# panel_jack_board.net
KiCad netlist of a schematic drawn in EAGLE
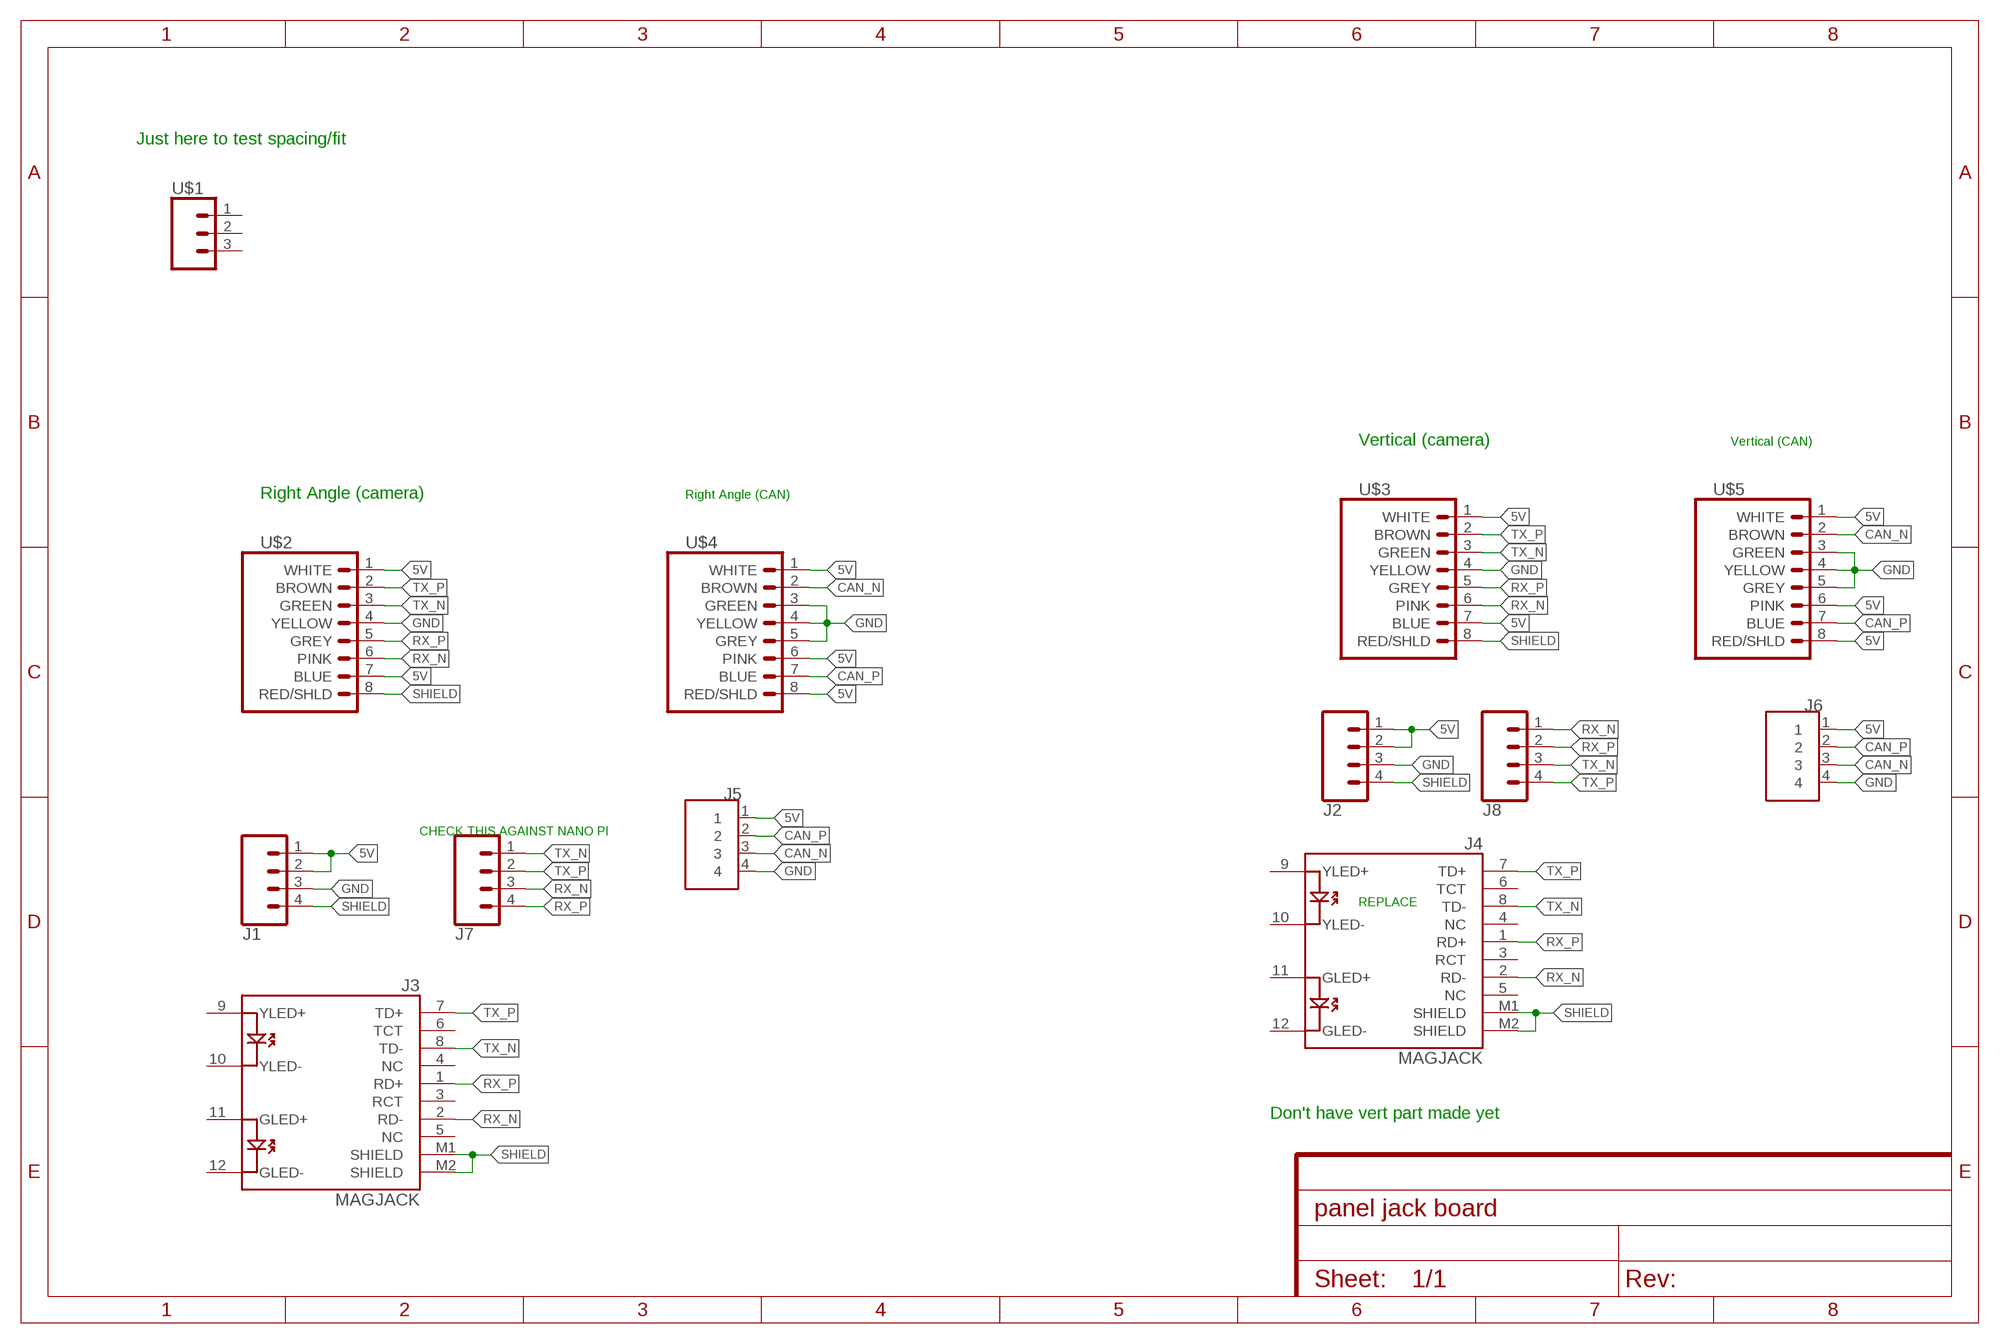
[diagram p0: schematic, sheet 1]

(export (version "E")
  (design (tool "Eeschema 10.0.6"))
  (components
    (comp (ref "J1")
      (value "PXC-PTSM-04-V-1778573")
      (footprint "eagle-import:PXC-PTSM-04-V-1778573")
      (libsource (lib "eagle-import") (part "PXC-PTSM-04-V-1778573"))
    )
    (comp (ref "J2")
      (value "PXC-PTSM-04-V-1778573")
      (footprint "eagle-import:PXC-PTSM-04-V-1778573")
      (libsource (lib "eagle-import") (part "PXC-PTSM-04-V-1778573"))
    )
    (comp (ref "J3")
      (value "MAGJACK")
      (footprint "eagle-import:MAGJACK")
      (libsource (lib "eagle-import") (part "MAGJACK"))
    )
    (comp (ref "J4")
      (value "MAGJACK")
      (footprint "eagle-import:MAGJACK")
      (libsource (lib "eagle-import") (part "MAGJACK"))
    )
    (comp (ref "J5")
      (value "284512-4")
      (footprint "eagle-import:TE_284512-4")
      (fields (field (name "MANUFACTURER") "TE"))
      (libsource (lib "eagle-import") (part "284512-4"))
    )
    (comp (ref "J6")
      (value "284512-4")
      (footprint "eagle-import:TE_284512-4")
      (fields (field (name "MANUFACTURER") "TE"))
      (libsource (lib "eagle-import") (part "284512-4"))
    )
    (comp (ref "J7")
      (value "PXC-PTSM-04-RA-1778641")
      (footprint "eagle-import:PXC-PTSM-04-RA-1778641")
      (libsource (lib "eagle-import") (part "PXC-PTSM-04-RA-1778641"))
    )
    (comp (ref "J8")
      (value "PXC-PTSM-04-V-1778573")
      (footprint "eagle-import:PXC-PTSM-04-V-1778573")
      (libsource (lib "eagle-import") (part "PXC-PTSM-04-V-1778573"))
    )
    (comp (ref "U$1")
      (value "BULGIN_BUC4000_3")
      (footprint "eagle-import:BULGIN_BUC4000_3")
      (libsource (lib "eagle-import") (part "BULGIN_BUC4000_3"))
    )
    (comp (ref "U$2")
      (value "BINDER_M12_RA_8")
      (footprint "eagle-import:BINDER_M12_RA_8")
      (libsource (lib "eagle-import") (part "BINDER_M12_RA_8"))
    )
    (comp (ref "U$3")
      (value "BINDER_M12_PAR_8_DIP")
      (footprint "eagle-import:BINDER_M12_PAR_8_DIP")
      (libsource (lib "eagle-import") (part "BINDER_M12_PAR_8_DIP"))
    )
    (comp (ref "U$4")
      (value "BINDER_M12_RA_8")
      (footprint "eagle-import:BINDER_M12_RA_8")
      (libsource (lib "eagle-import") (part "BINDER_M12_RA_8"))
    )
    (comp (ref "U$5")
      (value "BINDER_M12_PAR_8_DIP")
      (footprint "eagle-import:BINDER_M12_PAR_8_DIP")
      (libsource (lib "eagle-import") (part "BINDER_M12_PAR_8_DIP"))
    )
  )
  (nets
    (net (code "1") (name "5V") (class "Default")
      (node (ref "J1") (pin "1") (pinfunction "1_1") (pintype "passive"))
      (node (ref "J1") (pin "2") (pinfunction "2_2") (pintype "passive"))
      (node (ref "J2") (pin "1") (pinfunction "1_1") (pintype "passive"))
      (node (ref "J2") (pin "2") (pinfunction "2_2") (pintype "passive"))
      (node (ref "J5") (pin "1") (pinfunction "1_1") (pintype "passive"))
      (node (ref "J6") (pin "1") (pinfunction "1_1") (pintype "passive"))
      (node (ref "U$2") (pin "1") (pinfunction "WHITE_1") (pintype "passive"))
      (node (ref "U$2") (pin "7") (pinfunction "BLUE_7") (pintype "passive"))
      (node (ref "U$3") (pin "1") (pinfunction "WHITE_1") (pintype "passive"))
      (node (ref "U$3") (pin "7") (pinfunction "BLUE_7") (pintype "passive"))
      (node (ref "U$4") (pin "1") (pinfunction "WHITE_1") (pintype "passive"))
      (node (ref "U$4") (pin "6") (pinfunction "PINK_6") (pintype "passive"))
      (node (ref "U$4") (pin "8") (pinfunction "RED/SHLD_8") (pintype "passive"))
      (node (ref "U$5") (pin "1") (pinfunction "WHITE_1") (pintype "passive"))
      (node (ref "U$5") (pin "6") (pinfunction "PINK_6") (pintype "passive"))
      (node (ref "U$5") (pin "8") (pinfunction "RED/SHLD_8") (pintype "passive"))
    )
    (net (code "2") (name "CAN_N") (class "Default")
      (node (ref "J5") (pin "3") (pinfunction "3_3") (pintype "passive"))
      (node (ref "J6") (pin "3") (pinfunction "3_3") (pintype "passive"))
      (node (ref "U$4") (pin "2") (pinfunction "BROWN_2") (pintype "passive"))
      (node (ref "U$5") (pin "2") (pinfunction "BROWN_2") (pintype "passive"))
    )
    (net (code "3") (name "CAN_P") (class "Default")
      (node (ref "J5") (pin "2") (pinfunction "2_2") (pintype "passive"))
      (node (ref "J6") (pin "2") (pinfunction "2_2") (pintype "passive"))
      (node (ref "U$4") (pin "7") (pinfunction "BLUE_7") (pintype "passive"))
      (node (ref "U$5") (pin "7") (pinfunction "BLUE_7") (pintype "passive"))
    )
    (net (code "4") (name "GND") (class "Default")
      (node (ref "J1") (pin "3") (pinfunction "3_3") (pintype "passive"))
      (node (ref "J2") (pin "3") (pinfunction "3_3") (pintype "passive"))
      (node (ref "J5") (pin "4") (pinfunction "4_4") (pintype "passive"))
      (node (ref "J6") (pin "4") (pinfunction "4_4") (pintype "passive"))
      (node (ref "U$2") (pin "4") (pinfunction "YELLOW_4") (pintype "passive"))
      (node (ref "U$3") (pin "4") (pinfunction "YELLOW_4") (pintype "passive"))
      (node (ref "U$4") (pin "3") (pinfunction "GREEN_3") (pintype "passive"))
      (node (ref "U$4") (pin "4") (pinfunction "YELLOW_4") (pintype "passive"))
      (node (ref "U$4") (pin "5") (pinfunction "GREY_5") (pintype "passive"))
      (node (ref "U$5") (pin "3") (pinfunction "GREEN_3") (pintype "passive"))
      (node (ref "U$5") (pin "4") (pinfunction "YELLOW_4") (pintype "passive"))
      (node (ref "U$5") (pin "5") (pinfunction "GREY_5") (pintype "passive"))
    )
    (net (code "5") (name "RX_N") (class "Default")
      (node (ref "J3") (pin "2") (pinfunction "RD-_2") (pintype "bidirectional"))
      (node (ref "J4") (pin "2") (pinfunction "RD-_2") (pintype "bidirectional"))
      (node (ref "J7") (pin "3") (pinfunction "3_3") (pintype "passive"))
      (node (ref "J8") (pin "1") (pinfunction "1_1") (pintype "passive"))
      (node (ref "U$2") (pin "6") (pinfunction "PINK_6") (pintype "passive"))
      (node (ref "U$3") (pin "6") (pinfunction "PINK_6") (pintype "passive"))
    )
    (net (code "6") (name "RX_P") (class "Default")
      (node (ref "J3") (pin "1") (pinfunction "RD+_1") (pintype "bidirectional"))
      (node (ref "J4") (pin "1") (pinfunction "RD+_1") (pintype "bidirectional"))
      (node (ref "J7") (pin "4") (pinfunction "4_4") (pintype "passive"))
      (node (ref "J8") (pin "2") (pinfunction "2_2") (pintype "passive"))
      (node (ref "U$2") (pin "5") (pinfunction "GREY_5") (pintype "passive"))
      (node (ref "U$3") (pin "5") (pinfunction "GREY_5") (pintype "passive"))
    )
    (net (code "7") (name "SHIELD") (class "Default")
      (node (ref "J1") (pin "4") (pinfunction "4_4") (pintype "passive"))
      (node (ref "J2") (pin "4") (pinfunction "4_4") (pintype "passive"))
      (node (ref "J3") (pin "M1") (pinfunction "SHIELD_M1") (pintype "bidirectional"))
      (node (ref "J3") (pin "M2") (pinfunction "SHIELD_M2") (pintype "bidirectional"))
      (node (ref "J4") (pin "M1") (pinfunction "SHIELD_M1") (pintype "bidirectional"))
      (node (ref "J4") (pin "M2") (pinfunction "SHIELD_M2") (pintype "bidirectional"))
      (node (ref "U$2") (pin "8") (pinfunction "RED/SHLD_8") (pintype "passive"))
      (node (ref "U$3") (pin "8") (pinfunction "RED/SHLD_8") (pintype "passive"))
    )
    (net (code "8") (name "TX_N") (class "Default")
      (node (ref "J3") (pin "8") (pinfunction "TD-_8") (pintype "bidirectional"))
      (node (ref "J4") (pin "8") (pinfunction "TD-_8") (pintype "bidirectional"))
      (node (ref "J7") (pin "1") (pinfunction "1_1") (pintype "passive"))
      (node (ref "J8") (pin "3") (pinfunction "3_3") (pintype "passive"))
      (node (ref "U$2") (pin "3") (pinfunction "GREEN_3") (pintype "passive"))
      (node (ref "U$3") (pin "3") (pinfunction "GREEN_3") (pintype "passive"))
    )
    (net (code "9") (name "TX_P") (class "Default")
      (node (ref "J3") (pin "7") (pinfunction "TD+_7") (pintype "bidirectional"))
      (node (ref "J4") (pin "7") (pinfunction "TD+_7") (pintype "bidirectional"))
      (node (ref "J7") (pin "2") (pinfunction "2_2") (pintype "passive"))
      (node (ref "J8") (pin "4") (pinfunction "4_4") (pintype "passive"))
      (node (ref "U$2") (pin "2") (pinfunction "BROWN_2") (pintype "passive"))
      (node (ref "U$3") (pin "2") (pinfunction "BROWN_2") (pintype "passive"))
    )
    (net (code "10") (name "unconnected-(J3-GLED+-Pad11)") (class "Default")
      (node (ref "J3") (pin "11") (pinfunction "GLED+_11") (pintype "bidirectional"))
    )
    (net (code "11") (name "unconnected-(J3-GLED--Pad12)") (class "Default")
      (node (ref "J3") (pin "12") (pinfunction "GLED-_12") (pintype "bidirectional"))
    )
    (net (code "12") (name "unconnected-(J3-NC-Pad4)") (class "Default")
      (node (ref "J3") (pin "4") (pinfunction "NC_4") (pintype "bidirectional"))
    )
    (net (code "13") (name "unconnected-(J3-NC-Pad5)") (class "Default")
      (node (ref "J3") (pin "5") (pinfunction "NC_5") (pintype "bidirectional"))
    )
    (net (code "14") (name "unconnected-(J3-RCT-Pad3)") (class "Default")
      (node (ref "J3") (pin "3") (pinfunction "RCT_3") (pintype "bidirectional"))
    )
    (net (code "15") (name "unconnected-(J3-TCT-Pad6)") (class "Default")
      (node (ref "J3") (pin "6") (pinfunction "TCT_6") (pintype "bidirectional"))
    )
    (net (code "16") (name "unconnected-(J3-YLED+-Pad9)") (class "Default")
      (node (ref "J3") (pin "9") (pinfunction "YLED+_9") (pintype "bidirectional"))
    )
    (net (code "17") (name "unconnected-(J3-YLED--Pad10)") (class "Default")
      (node (ref "J3") (pin "10") (pinfunction "YLED-_10") (pintype "bidirectional"))
    )
    (net (code "18") (name "unconnected-(J4-GLED+-Pad11)") (class "Default")
      (node (ref "J4") (pin "11") (pinfunction "GLED+_11") (pintype "bidirectional"))
    )
    (net (code "19") (name "unconnected-(J4-GLED--Pad12)") (class "Default")
      (node (ref "J4") (pin "12") (pinfunction "GLED-_12") (pintype "bidirectional"))
    )
    (net (code "20") (name "unconnected-(J4-NC-Pad4)") (class "Default")
      (node (ref "J4") (pin "4") (pinfunction "NC_4") (pintype "bidirectional"))
    )
    (net (code "21") (name "unconnected-(J4-NC-Pad5)") (class "Default")
      (node (ref "J4") (pin "5") (pinfunction "NC_5") (pintype "bidirectional"))
    )
    (net (code "22") (name "unconnected-(J4-RCT-Pad3)") (class "Default")
      (node (ref "J4") (pin "3") (pinfunction "RCT_3") (pintype "bidirectional"))
    )
    (net (code "23") (name "unconnected-(J4-TCT-Pad6)") (class "Default")
      (node (ref "J4") (pin "6") (pinfunction "TCT_6") (pintype "bidirectional"))
    )
    (net (code "24") (name "unconnected-(J4-YLED+-Pad9)") (class "Default")
      (node (ref "J4") (pin "9") (pinfunction "YLED+_9") (pintype "bidirectional"))
    )
    (net (code "25") (name "unconnected-(J4-YLED--Pad10)") (class "Default")
      (node (ref "J4") (pin "10") (pinfunction "YLED-_10") (pintype "bidirectional"))
    )
    (net (code "26") (name "unconnected-(U$1-Pad1)") (class "Default")
      (node (ref "U$1") (pin "1") (pinfunction "1_1") (pintype "passive"))
    )
    (net (code "27") (name "unconnected-(U$1-Pad2)") (class "Default")
      (node (ref "U$1") (pin "2") (pinfunction "2_2") (pintype "passive"))
    )
    (net (code "28") (name "unconnected-(U$1-Pad3)") (class "Default")
      (node (ref "U$1") (pin "3") (pinfunction "3_3") (pintype "passive"))
    )
  )
)
